# beacon.net
KiCad netlist of a schematic drawn in EAGLE
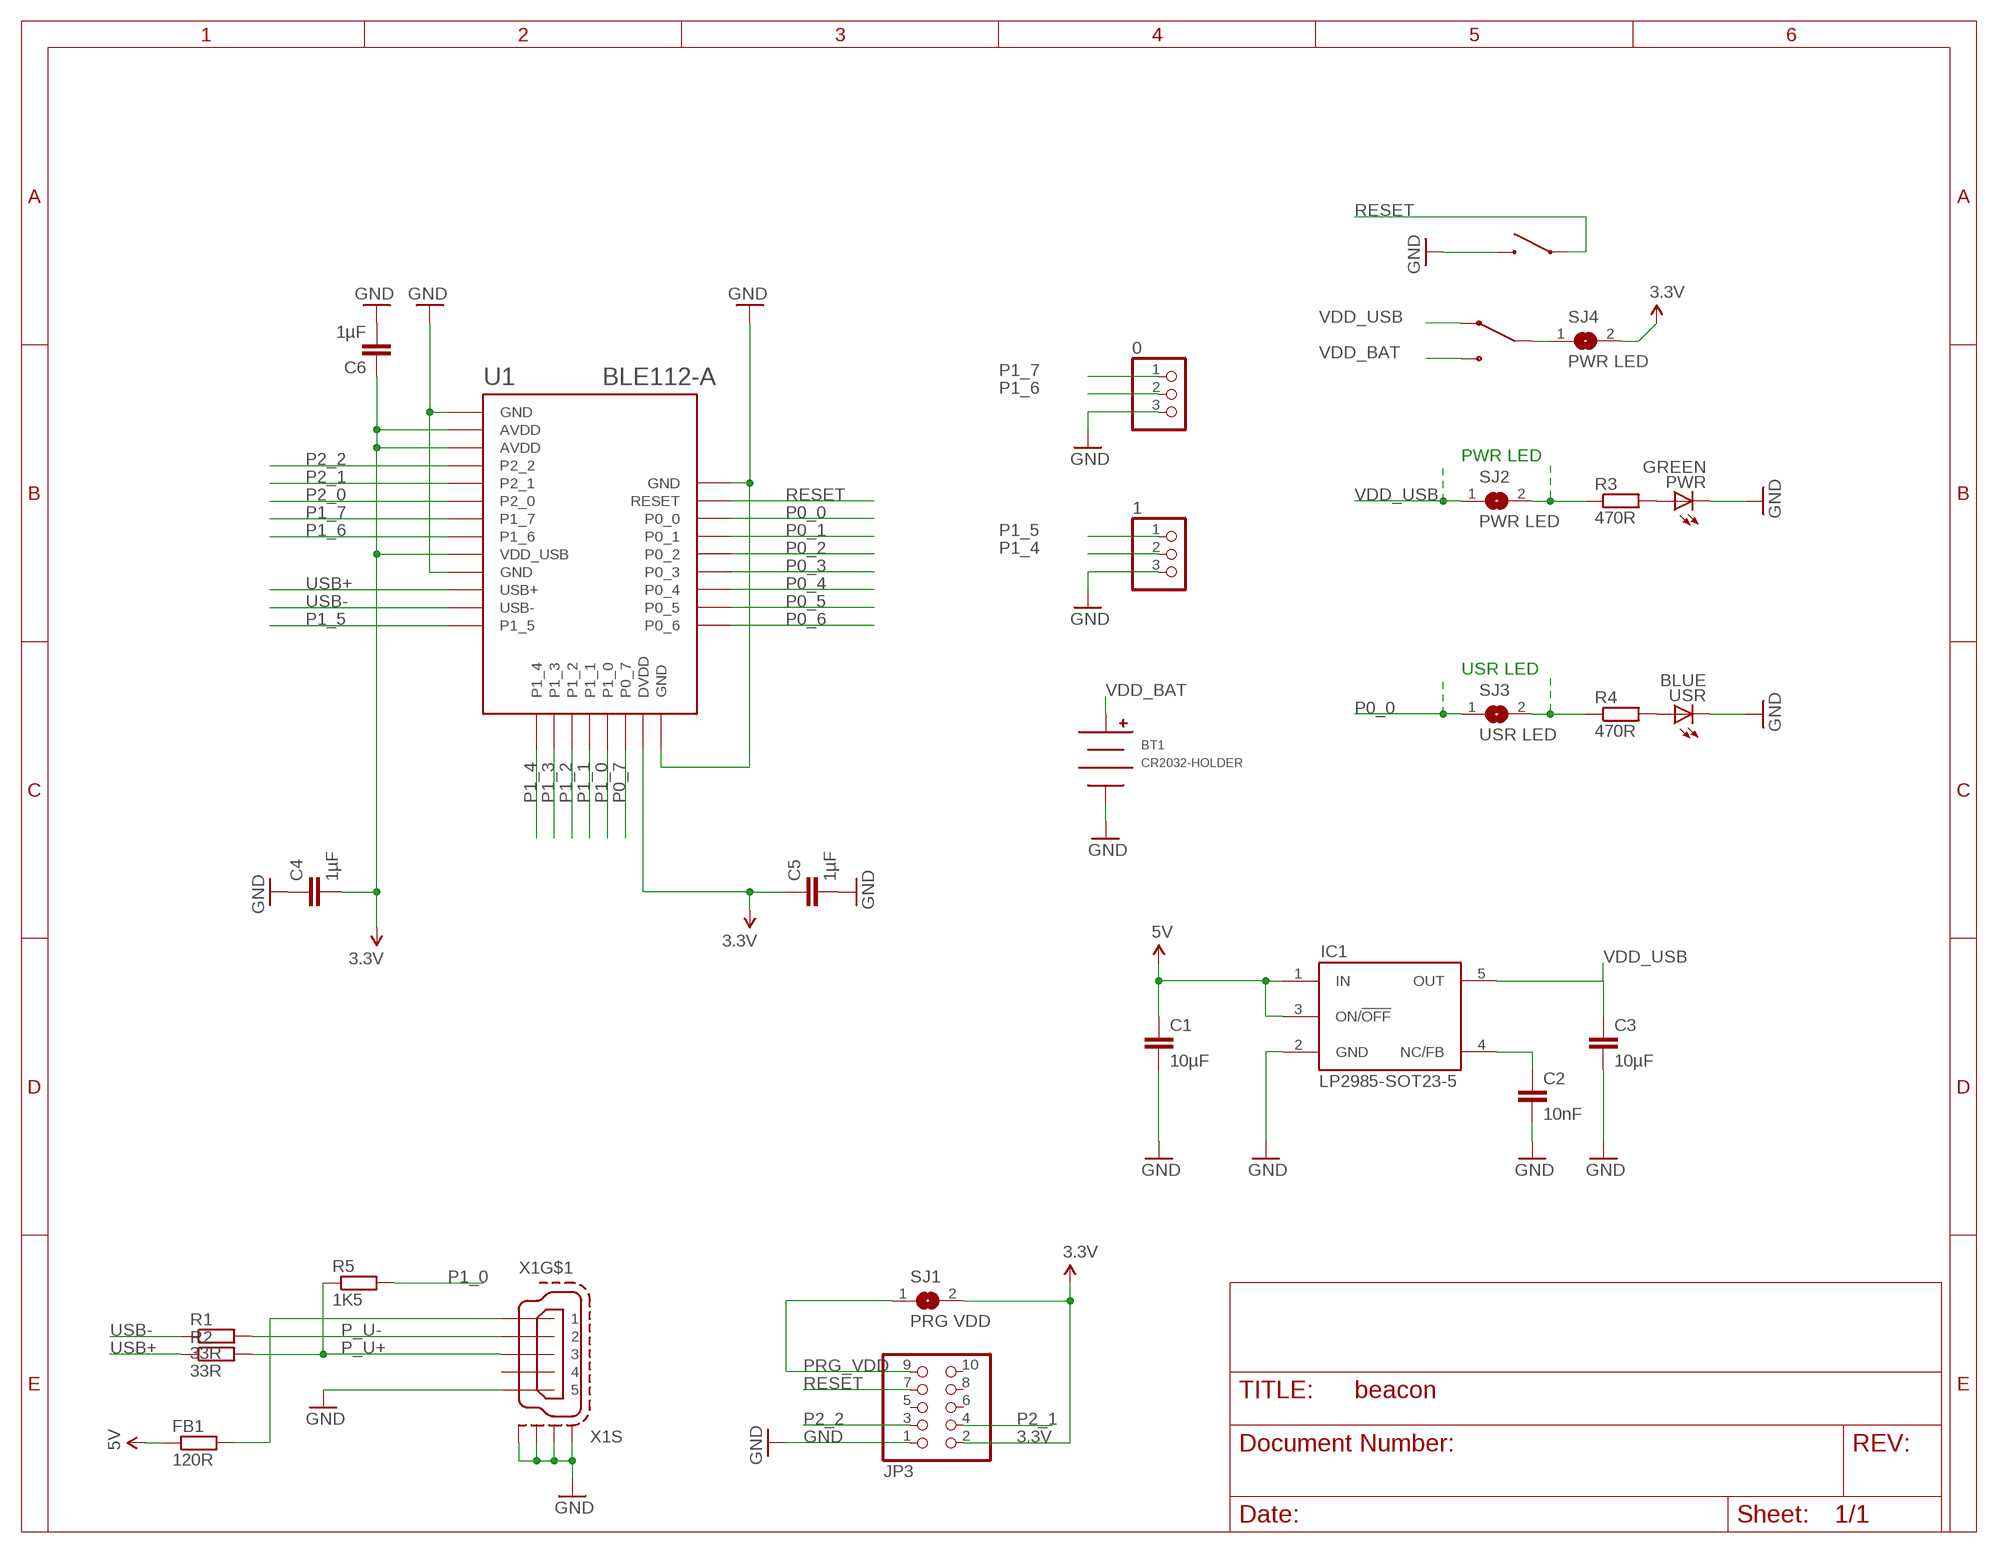
[diagram p0: schematic, sheet 1]

(export (version "E")
  (design (tool "Eeschema 10.0.6"))
  (components
    (comp (ref "0")
      (value "HEADER-1X3ROUND")
      (footprint "eagle-import:1X03_ROUND")
      (libsource (lib "eagle-import") (part "HEADER-1X3ROUND"))
    )
    (comp (ref "1")
      (value "HEADER-1X3ROUND")
      (footprint "eagle-import:1X03_ROUND")
      (libsource (lib "eagle-import") (part "HEADER-1X3ROUND"))
    )
    (comp (ref "BT1")
      (value "CR2032-HOLDER")
      (footprint "eagle-import:CH28-2032LF")
      (libsource (lib "eagle-import") (part "CR2032-HOLDER"))
    )
    (comp (ref "C1")
      (value "10µF")
      (footprint "eagle-import:C0603")
      (libsource (lib "eagle-import") (part "C-EUC0603"))
    )
    (comp (ref "C2")
      (value "10nF")
      (footprint "eagle-import:C0603")
      (libsource (lib "eagle-import") (part "C-EUC0603"))
    )
    (comp (ref "C3")
      (value "10µF")
      (footprint "eagle-import:C0603")
      (libsource (lib "eagle-import") (part "C-EUC0603"))
    )
    (comp (ref "C4")
      (value "1µF")
      (footprint "eagle-import:C0603")
      (libsource (lib "eagle-import") (part "C-EUC0603"))
    )
    (comp (ref "C5")
      (value "1µF")
      (footprint "eagle-import:C0603")
      (libsource (lib "eagle-import") (part "C-EUC0603"))
    )
    (comp (ref "C6")
      (value "1µF")
      (footprint "eagle-import:C0603")
      (libsource (lib "eagle-import") (part "C-EUC0603"))
    )
    (comp (ref "FB1")
      (value "120R")
      (footprint "eagle-import:R0603")
      (libsource (lib "eagle-import") (part "R-EU_R0603"))
    )
    (comp (ref "IC1")
      (value "LP2985-SOT23-5")
      (footprint "eagle-import:SOT23-5")
      (libsource (lib "eagle-import") (part "LP2985-SOT23-5"))
    )
    (comp (ref "JP3")
      (value "ARM-JTAG_1.27-SMD")
      (footprint "eagle-import:20021121-10010XXLF")
      (libsource (lib "eagle-import") (part "ARM-JTAG_1.27-SMD"))
    )
    (comp (ref "PWR")
      (value "GREEN")
      (footprint "eagle-import:CHIPLED_0805")
      (libsource (lib "eagle-import") (part "LEDCHIPLED_0805"))
    )
    (comp (ref "R1")
      (value "33R")
      (footprint "eagle-import:R0603")
      (libsource (lib "eagle-import") (part "R-EU_R0603"))
    )
    (comp (ref "R2")
      (value "33R")
      (footprint "eagle-import:R0603")
      (libsource (lib "eagle-import") (part "R-EU_R0603"))
    )
    (comp (ref "R3")
      (value "470R")
      (footprint "eagle-import:R0603")
      (libsource (lib "eagle-import") (part "R-EU_R0603"))
    )
    (comp (ref "R4")
      (value "470R")
      (footprint "eagle-import:R0603")
      (libsource (lib "eagle-import") (part "R-EU_R0603"))
    )
    (comp (ref "R5")
      (value "1K5")
      (footprint "eagle-import:R0603")
      (libsource (lib "eagle-import") (part "R-EU_R0603"))
    )
    (comp (ref "RST")
      (value "TACT-SWITCH-40-40")
      (footprint "eagle-import:40-40")
      (libsource (lib "eagle-import") (part "TACT-SWITCH-40-40"))
    )
    (comp (ref "SJ1")
      (value "PRG VDD")
      (footprint "eagle-import:SJ")
      (libsource (lib "eagle-import") (part "SJ"))
    )
    (comp (ref "SJ2")
      (value "PWR LED")
      (footprint "eagle-import:SJ")
      (libsource (lib "eagle-import") (part "SJ"))
    )
    (comp (ref "SJ3")
      (value "USR LED")
      (footprint "eagle-import:SJ")
      (libsource (lib "eagle-import") (part "SJ"))
    )
    (comp (ref "SJ4")
      (value "PWR LED")
      (footprint "eagle-import:SJ")
      (libsource (lib "eagle-import") (part "SJ"))
    )
    (comp (ref "U$1")
      (value "1P2T")
      (footprint "eagle-import:1P2T-ON-ON")
      (libsource (lib "eagle-import") (part "1P2T"))
    )
    (comp (ref "U1")
      (value "BLE112-A")
      (footprint "eagle-import:BLE112-A")
      (libsource (lib "eagle-import") (part "BLE112-A-VISUAL"))
    )
    (comp (ref "USR")
      (value "BLUE")
      (footprint "eagle-import:CHIPLED_0805")
      (libsource (lib "eagle-import") (part "LEDCHIPLED_0805"))
    )
    (comp (ref "X1")
      (value "MINI-USB-SCHIELD-32005-301")
      (footprint "eagle-import:32005-301")
      (libsource (lib "eagle-import") (part "MINI-USB-SCHIELD-32005-301"))
    )
  )
  (nets
    (net (code "1") (name "/P0_0") (class "Default")
      (node (ref "SJ3") (pin "1") (pinfunction "1_1") (pintype "passive"))
      (node (ref "U1") (pin "P0_0") (pinfunction "P0_0_P0_0") (pintype "bidirectional"))
    )
    (net (code "2") (name "/P0_1") (class "Default")
      (node (ref "U1") (pin "P0_1") (pinfunction "P0_1_P0_1") (pintype "bidirectional"))
    )
    (net (code "3") (name "/P0_2") (class "Default")
      (node (ref "U1") (pin "P0_2") (pinfunction "P0_2_P0_2") (pintype "bidirectional"))
    )
    (net (code "4") (name "/P0_3") (class "Default")
      (node (ref "U1") (pin "P0_3") (pinfunction "P0_3_P0_3") (pintype "bidirectional"))
    )
    (net (code "5") (name "/P0_4") (class "Default")
      (node (ref "U1") (pin "P0_4") (pinfunction "P0_4_P0_4") (pintype "bidirectional"))
    )
    (net (code "6") (name "/P0_5") (class "Default")
      (node (ref "U1") (pin "P0_5") (pinfunction "P0_5_P0_5") (pintype "bidirectional"))
    )
    (net (code "7") (name "/P0_6") (class "Default")
      (node (ref "U1") (pin "P0_6") (pinfunction "P0_6_P0_6") (pintype "bidirectional"))
    )
    (net (code "8") (name "/P0_7") (class "Default")
      (node (ref "U1") (pin "P0_7") (pinfunction "P0_7_P0_7") (pintype "bidirectional"))
    )
    (net (code "9") (name "/P1_0") (class "Default")
      (node (ref "R5") (pin "2") (pinfunction "2_2") (pintype "passive"))
      (node (ref "U1") (pin "P1_0") (pinfunction "P1_0_P1_0") (pintype "bidirectional"))
    )
    (net (code "10") (name "/P1_1") (class "Default")
      (node (ref "U1") (pin "P1_1") (pinfunction "P1_1_P1_1") (pintype "bidirectional"))
    )
    (net (code "11") (name "/P1_2") (class "Default")
      (node (ref "U1") (pin "P1_2") (pinfunction "P1_2_P1_2") (pintype "bidirectional"))
    )
    (net (code "12") (name "/P1_3") (class "Default")
      (node (ref "U1") (pin "P1_3") (pinfunction "P1_3_P1_3") (pintype "bidirectional"))
    )
    (net (code "13") (name "/P1_4") (class "Default")
      (node (ref "1") (pin "2") (pinfunction "2_2") (pintype "passive"))
      (node (ref "U1") (pin "P1_4") (pinfunction "P1_4_P1_4") (pintype "bidirectional"))
    )
    (net (code "14") (name "/P1_5") (class "Default")
      (node (ref "1") (pin "1") (pinfunction "1_1") (pintype "passive"))
      (node (ref "U1") (pin "P1_5") (pinfunction "P1_5_P1_5") (pintype "bidirectional"))
    )
    (net (code "15") (name "/P1_6") (class "Default")
      (node (ref "0") (pin "2") (pinfunction "2_2") (pintype "passive"))
      (node (ref "U1") (pin "P1_6") (pinfunction "P1_6_P1_6") (pintype "bidirectional"))
    )
    (net (code "16") (name "/P1_7") (class "Default")
      (node (ref "0") (pin "1") (pinfunction "1_1") (pintype "passive"))
      (node (ref "U1") (pin "P1_7") (pinfunction "P1_7_P1_7") (pintype "bidirectional"))
    )
    (net (code "17") (name "/P2_0") (class "Default")
      (node (ref "U1") (pin "P2_0") (pinfunction "P2_0_P2_0") (pintype "bidirectional"))
    )
    (net (code "18") (name "/P2_1") (class "Default")
      (node (ref "JP3") (pin "4") (pinfunction "4_4") (pintype "passive"))
      (node (ref "U1") (pin "P2_1") (pinfunction "P2_1_P2_1") (pintype "bidirectional"))
    )
    (net (code "19") (name "/P2_2") (class "Default")
      (node (ref "JP3") (pin "3") (pinfunction "3_3") (pintype "passive"))
      (node (ref "U1") (pin "P2_2") (pinfunction "P2_2_P2_2") (pintype "bidirectional"))
    )
    (net (code "20") (name "/PRG_VDD") (class "Default")
      (node (ref "JP3") (pin "9") (pinfunction "9_9") (pintype "passive"))
      (node (ref "SJ1") (pin "1") (pinfunction "1_1") (pintype "passive"))
    )
    (net (code "21") (name "/P_U+") (class "Default")
      (node (ref "R2") (pin "2") (pinfunction "2_2") (pintype "passive"))
      (node (ref "R5") (pin "1") (pinfunction "1_1") (pintype "passive"))
      (node (ref "X1") (pin "3") (pinfunction "3_3") (pintype "passive"))
    )
    (net (code "22") (name "/P_U-") (class "Default")
      (node (ref "R1") (pin "2") (pinfunction "2_2") (pintype "passive"))
      (node (ref "X1") (pin "2") (pinfunction "2_2") (pintype "passive"))
    )
    (net (code "23") (name "/RESET") (class "Default")
      (node (ref "JP3") (pin "7") (pinfunction "7_7") (pintype "passive"))
      (node (ref "RST") (pin "3") (pinfunction "P$2_3") (pintype "bidirectional"))
      (node (ref "RST") (pin "4") (pinfunction "P$2_4") (pintype "bidirectional"))
      (node (ref "U1") (pin "RESET") (pinfunction "RESET_RESET") (pintype "input"))
    )
    (net (code "24") (name "/USB+") (class "Default")
      (node (ref "R2") (pin "1") (pinfunction "1_1") (pintype "passive"))
      (node (ref "U1") (pin "USB+") (pinfunction "USB+_USB+") (pintype "bidirectional"))
    )
    (net (code "25") (name "/USB-") (class "Default")
      (node (ref "R1") (pin "1") (pinfunction "1_1") (pintype "passive"))
      (node (ref "U1") (pin "USB-") (pinfunction "USB-_USB-") (pintype "bidirectional"))
    )
    (net (code "26") (name "/VDD_BAT") (class "Default")
      (node (ref "BT1") (pin "POS") (pinfunction "POS_POS") (pintype "bidirectional"))
      (node (ref "U$1") (pin "3") (pinfunction "P$3_3") (pintype "bidirectional"))
    )
    (net (code "27") (name "/VDD_USB") (class "Default")
      (node (ref "C3") (pin "1") (pinfunction "1_1") (pintype "passive"))
      (node (ref "IC1") (pin "5") (pinfunction "OUT_5") (pintype "bidirectional"))
      (node (ref "SJ2") (pin "1") (pinfunction "1_1") (pintype "passive"))
      (node (ref "U$1") (pin "1") (pinfunction "P$1_1") (pintype "bidirectional"))
    )
    (net (code "28") (name "3.3V") (class "Default")
      (node (ref "C4") (pin "2") (pinfunction "2_2") (pintype "passive"))
      (node (ref "C5") (pin "1") (pinfunction "1_1") (pintype "passive"))
      (node (ref "C6") (pin "1") (pinfunction "1_1") (pintype "passive"))
      (node (ref "JP3") (pin "2") (pinfunction "2_2") (pintype "passive"))
      (node (ref "SJ1") (pin "2") (pinfunction "2_2") (pintype "passive"))
      (node (ref "SJ4") (pin "2") (pinfunction "2_2") (pintype "passive"))
      (node (ref "U1") (pin "AVDD1") (pinfunction "AVDD_AVDD1") (pintype "power_in"))
      (node (ref "U1") (pin "AVDD2") (pinfunction "AVDD_AVDD2") (pintype "power_in"))
      (node (ref "U1") (pin "DVDD") (pinfunction "DVDD_DVDD") (pintype "power_in"))
      (node (ref "U1") (pin "VDD_USB") (pinfunction "VDD_USB_VDD_USB") (pintype "power_in"))
    )
    (net (code "29") (name "5V") (class "Default")
      (node (ref "C1") (pin "1") (pinfunction "1_1") (pintype "passive"))
      (node (ref "FB1") (pin "1") (pinfunction "1_1") (pintype "passive"))
      (node (ref "IC1") (pin "1") (pinfunction "IN_1") (pintype "bidirectional"))
      (node (ref "IC1") (pin "3") (pinfunction "ON/~{OFF}_3") (pintype "bidirectional"))
    )
    (net (code "30") (name "GND") (class "Default")
      (node (ref "0") (pin "3") (pinfunction "3_3") (pintype "passive"))
      (node (ref "1") (pin "3") (pinfunction "3_3") (pintype "passive"))
      (node (ref "BT1") (pin "NEG") (pinfunction "NEG_NEG") (pintype "bidirectional"))
      (node (ref "C1") (pin "2") (pinfunction "2_2") (pintype "passive"))
      (node (ref "C2") (pin "2") (pinfunction "2_2") (pintype "passive"))
      (node (ref "C3") (pin "2") (pinfunction "2_2") (pintype "passive"))
      (node (ref "C4") (pin "1") (pinfunction "1_1") (pintype "passive"))
      (node (ref "C5") (pin "2") (pinfunction "2_2") (pintype "passive"))
      (node (ref "C6") (pin "2") (pinfunction "2_2") (pintype "passive"))
      (node (ref "IC1") (pin "2") (pinfunction "GND_2") (pintype "bidirectional"))
      (node (ref "JP3") (pin "1") (pinfunction "1_1") (pintype "passive"))
      (node (ref "PWR") (pin "C") (pinfunction "C_C") (pintype "passive"))
      (node (ref "RST") (pin "1") (pinfunction "P$1_1") (pintype "bidirectional"))
      (node (ref "RST") (pin "2") (pinfunction "P$1_2") (pintype "bidirectional"))
      (node (ref "U1") (pin "GND1") (pinfunction "GND_GND1") (pintype "power_in"))
      (node (ref "U1") (pin "GND2") (pinfunction "GND_GND2") (pintype "power_in"))
      (node (ref "U1") (pin "GND3") (pinfunction "GND_GND3") (pintype "power_in"))
      (node (ref "U1") (pin "GND4") (pinfunction "GND_GND4") (pintype "power_in"))
      (node (ref "USR") (pin "C") (pinfunction "C_C") (pintype "passive"))
      (node (ref "X1") (pin "5") (pinfunction "5_5") (pintype "passive"))
      (node (ref "X1") (pin "M1") (pinfunction "S1_M1") (pintype "passive"))
      (node (ref "X1") (pin "M2") (pinfunction "S2_M2") (pintype "passive"))
      (node (ref "X1") (pin "M3") (pinfunction "S3_M3") (pintype "passive"))
      (node (ref "X1") (pin "M4") (pinfunction "S4_M4") (pintype "passive"))
    )
    (net (code "31") (name "Net-(FB1-Pad2)") (class "Default")
      (node (ref "FB1") (pin "2") (pinfunction "2_2") (pintype "passive"))
      (node (ref "X1") (pin "1") (pinfunction "1_1") (pintype "passive"))
    )
    (net (code "32") (name "Net-(IC1-NC{slash}FB)") (class "Default")
      (node (ref "C2") (pin "1") (pinfunction "1_1") (pintype "passive"))
      (node (ref "IC1") (pin "4") (pinfunction "NC/FB_4") (pintype "bidirectional"))
    )
    (net (code "33") (name "Net-(PWR-PadA)") (class "Default")
      (node (ref "PWR") (pin "A") (pinfunction "A_A") (pintype "passive"))
      (node (ref "R3") (pin "2") (pinfunction "2_2") (pintype "passive"))
    )
    (net (code "34") (name "Net-(R3-Pad1)") (class "Default")
      (node (ref "R3") (pin "1") (pinfunction "1_1") (pintype "passive"))
      (node (ref "SJ2") (pin "2") (pinfunction "2_2") (pintype "passive"))
    )
    (net (code "35") (name "Net-(R4-Pad1)") (class "Default")
      (node (ref "R4") (pin "1") (pinfunction "1_1") (pintype "passive"))
      (node (ref "SJ3") (pin "2") (pinfunction "2_2") (pintype "passive"))
    )
    (net (code "36") (name "Net-(R4-Pad2)") (class "Default")
      (node (ref "R4") (pin "2") (pinfunction "2_2") (pintype "passive"))
      (node (ref "USR") (pin "A") (pinfunction "A_A") (pintype "passive"))
    )
    (net (code "37") (name "Net-(U$1-P$2)") (class "Default")
      (node (ref "SJ4") (pin "1") (pinfunction "1_1") (pintype "passive"))
      (node (ref "U$1") (pin "2") (pinfunction "P$2_2") (pintype "bidirectional"))
    )
    (net (code "38") (name "unconnected-(JP3-Pad5)") (class "Default")
      (node (ref "JP3") (pin "5") (pinfunction "5_5") (pintype "passive"))
    )
    (net (code "39") (name "unconnected-(JP3-Pad6)") (class "Default")
      (node (ref "JP3") (pin "6") (pinfunction "6_6") (pintype "passive"))
    )
    (net (code "40") (name "unconnected-(JP3-Pad8)") (class "Default")
      (node (ref "JP3") (pin "8") (pinfunction "8_8") (pintype "passive"))
    )
    (net (code "41") (name "unconnected-(JP3-Pad10)") (class "Default")
      (node (ref "JP3") (pin "10") (pinfunction "10_10") (pintype "passive"))
    )
    (net (code "42") (name "unconnected-(X1-Pad4)") (class "Default")
      (node (ref "X1") (pin "4") (pinfunction "4_4") (pintype "passive"))
    )
  )
)
